# ESP-AXA.net
KiCad netlist of a schematic drawn in EAGLE
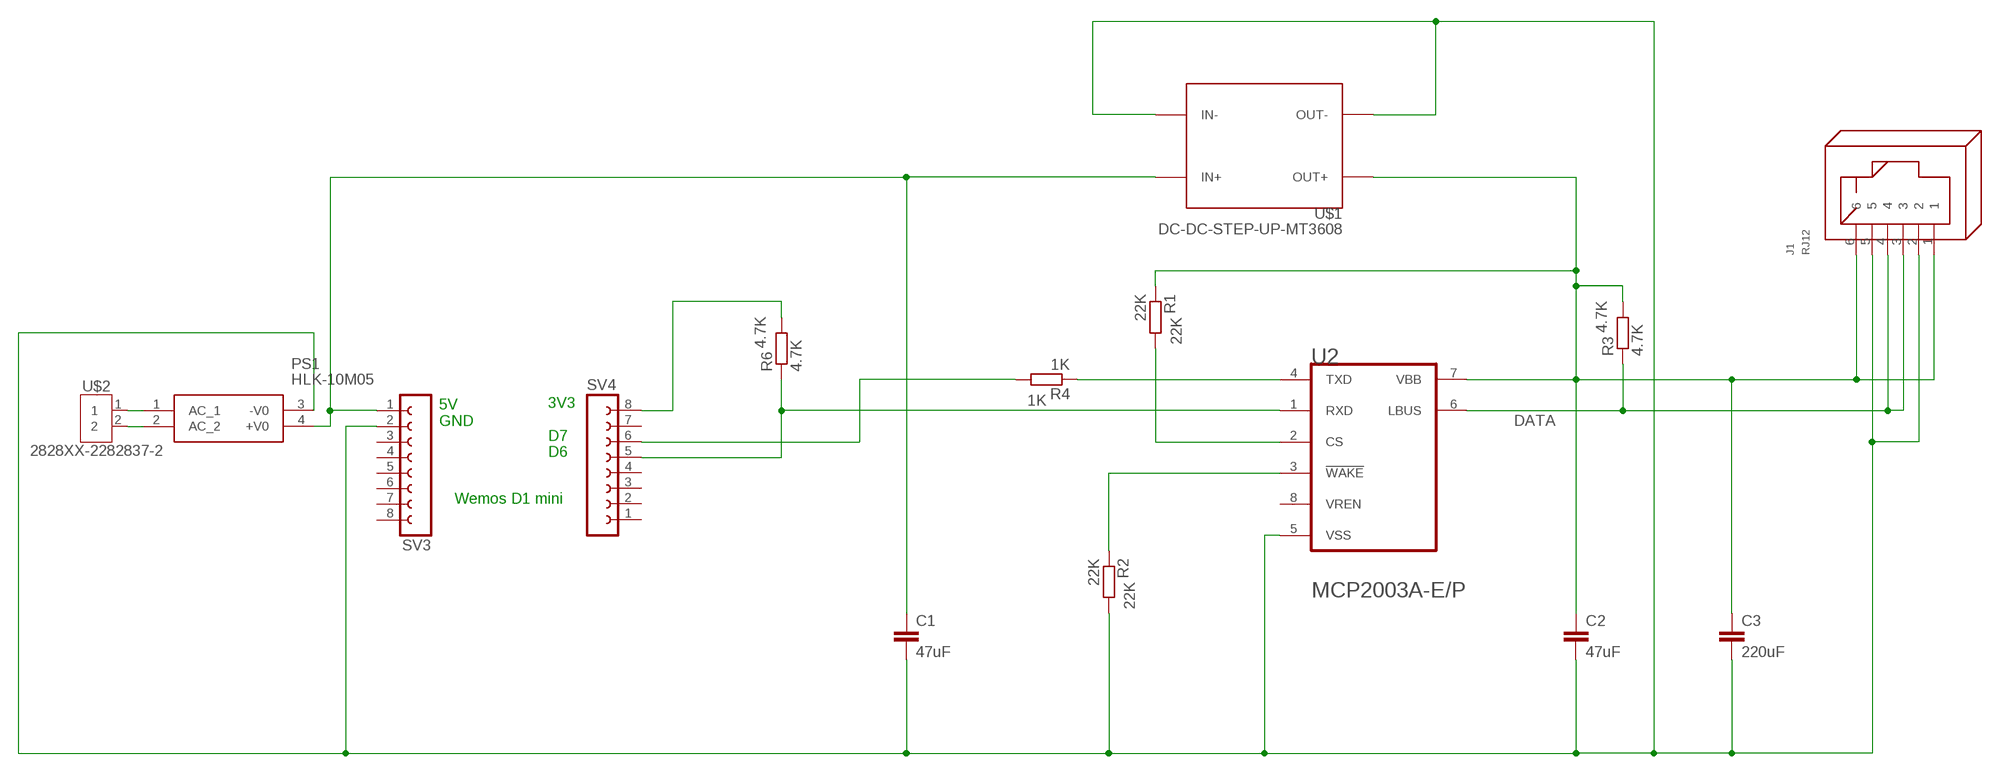
[diagram p0: schematic, sheet 1]

(export (version "E")
  (design (tool "Eeschema 10.0.6"))
  (components
    (comp (ref "C1")
      (value "47uF")
      (footprint "eagle-import:C7.5B3")
      (libsource (lib "eagle-import") (part "C7.5/3"))
    )
    (comp (ref "C2")
      (value "47uF")
      (footprint "eagle-import:C7.5B3")
      (libsource (lib "eagle-import") (part "C7.5/3"))
    )
    (comp (ref "C3")
      (value "220uF")
      (footprint "eagle-import:C7.5B3")
      (libsource (lib "eagle-import") (part "C7.5/3"))
    )
    (comp (ref "J1")
      (value "RJ12")
      (footprint "eagle-import:RJ12")
      (libsource (lib "eagle-import") (part "RJ12"))
    )
    (comp (ref "PS1")
      (value "HLK-10M05")
      (footprint "eagle-import:HLK10M05")
      (libsource (lib "eagle-import") (part "HLK-10M05"))
    )
    (comp (ref "R1")
      (value "22K")
      (footprint "eagle-import:0204V")
      (fields (field (name "R6") "22K"))
      (libsource (lib "eagle-import") (part "R-EU_0204/2V"))
    )
    (comp (ref "R2")
      (value "22K")
      (footprint "eagle-import:0204V")
      (fields (field (name "R6") "22K"))
      (libsource (lib "eagle-import") (part "R-EU_0204/2V"))
    )
    (comp (ref "R3")
      (value "4.7K")
      (footprint "eagle-import:0204V")
      (fields (field (name "R6") "4.7K"))
      (libsource (lib "eagle-import") (part "R-EU_0204/2V"))
    )
    (comp (ref "R4")
      (value "1K")
      (footprint "eagle-import:0204V")
      (fields (field (name "R6") "1K"))
      (libsource (lib "eagle-import") (part "R-EU_0204/2V"))
    )
    (comp (ref "R6")
      (value "4.7K")
      (footprint "eagle-import:0204V")
      (fields (field (name "R6") "4.7K"))
      (libsource (lib "eagle-import") (part "R-EU_0204/2V"))
    )
    (comp (ref "SV3")
      (value "FE08-1")
      (footprint "eagle-import:FE08")
      (libsource (lib "eagle-import") (part "FE08-1"))
    )
    (comp (ref "SV4")
      (value "FE08-1")
      (footprint "eagle-import:FE08")
      (libsource (lib "eagle-import") (part "FE08-1"))
    )
    (comp (ref "U$1")
      (value "DC-DC-STEP-UP-MT3608")
      (footprint "eagle-import:DC-DC-STEP-UP-MT3608")
      (libsource (lib "eagle-import") (part "DC-DC-STEP-UP-MT3608"))
    )
    (comp (ref "U$2")
      (value "2828XX-2282837-2")
      (footprint "eagle-import:TERMBLK_508-2N")
      (fields (field (name "MANUFACTURER") "TE Connectivity") (field (name "MPN") "282837-2"))
      (libsource (lib "eagle-import") (part "2828XX-2282837-2"))
    )
    (comp (ref "U2")
      (value "MICROCHIP_MCP2003A-E-PMICROCHIP_MCP2003A-E-P_0_0")
      (footprint "eagle-import:MICROCHIP_MCP2003A-E-P_0")
      (fields (field (name "MF") "Microchip") (field (name "MPN") "MCP2003A-E/P"))
      (libsource (lib "eagle-import") (part "MICROCHIP_MCP2003A-E-PMICROCHIP_MCP2003A-E-P_0_0"))
    )
  )
  (nets
    (net (code "1") (name "/DATA") (class "Default")
      (node (ref "J1") (pin "3") (pinfunction "3_3") (pintype "bidirectional"))
      (node (ref "J1") (pin "4") (pinfunction "4_4") (pintype "bidirectional"))
      (node (ref "R3") (pin "1") (pinfunction "1_1") (pintype "passive"))
      (node (ref "U2") (pin "6") (pinfunction "LBUS_6") (pintype "bidirectional"))
    )
    (net (code "2") (name "Net-(PS1-+V0)") (class "Default")
      (node (ref "C1") (pin "1") (pinfunction "1_1") (pintype "passive"))
      (node (ref "PS1") (pin "4") (pinfunction "+V0_4") (pintype "bidirectional"))
      (node (ref "SV3") (pin "1") (pinfunction "1_1") (pintype "passive"))
      (node (ref "U$1") (pin "IN+") (pinfunction "IN+_IN+") (pintype "bidirectional"))
    )
    (net (code "3") (name "Net-(PS1--V0)") (class "Default")
      (node (ref "C1") (pin "2") (pinfunction "2_2") (pintype "passive"))
      (node (ref "C2") (pin "2") (pinfunction "2_2") (pintype "passive"))
      (node (ref "C3") (pin "2") (pinfunction "2_2") (pintype "passive"))
      (node (ref "J1") (pin "2") (pinfunction "2_2") (pintype "bidirectional"))
      (node (ref "J1") (pin "5") (pinfunction "5_5") (pintype "bidirectional"))
      (node (ref "PS1") (pin "3") (pinfunction "-V0_3") (pintype "bidirectional"))
      (node (ref "R2") (pin "2") (pinfunction "2_2") (pintype "passive"))
      (node (ref "SV3") (pin "2") (pinfunction "2_2") (pintype "passive"))
      (node (ref "U$1") (pin "IN-") (pinfunction "IN-_IN-") (pintype "bidirectional"))
      (node (ref "U$1") (pin "OUT-") (pinfunction "OUT-_OUT-") (pintype "bidirectional"))
      (node (ref "U2") (pin "5") (pinfunction "VSS_5") (pintype "power_in"))
    )
    (net (code "4") (name "Net-(PS1-AC_1)") (class "Default")
      (node (ref "PS1") (pin "1") (pinfunction "AC_1_1") (pintype "bidirectional"))
      (node (ref "U$2") (pin "1") (pinfunction "1_1") (pintype "bidirectional"))
    )
    (net (code "5") (name "Net-(PS1-AC_2)") (class "Default")
      (node (ref "PS1") (pin "2") (pinfunction "AC_2_2") (pintype "bidirectional"))
      (node (ref "U$2") (pin "2") (pinfunction "2_2") (pintype "bidirectional"))
    )
    (net (code "6") (name "Net-(R4-Pad2)") (class "Default")
      (node (ref "R4") (pin "2") (pinfunction "2_2") (pintype "passive"))
      (node (ref "SV4") (pin "6") (pinfunction "6_6") (pintype "passive"))
    )
    (net (code "7") (name "Net-(R6-Pad2)") (class "Default")
      (node (ref "R6") (pin "2") (pinfunction "2_2") (pintype "passive"))
      (node (ref "SV4") (pin "8") (pinfunction "8_8") (pintype "passive"))
    )
    (net (code "8") (name "Net-(U2-CS)") (class "Default")
      (node (ref "R1") (pin "2") (pinfunction "2_2") (pintype "passive"))
      (node (ref "U2") (pin "2") (pinfunction "CS_2") (pintype "input"))
    )
    (net (code "9") (name "Net-(U2-RXD)") (class "Default")
      (node (ref "R6") (pin "1") (pinfunction "1_1") (pintype "passive"))
      (node (ref "SV4") (pin "5") (pinfunction "5_5") (pintype "passive"))
      (node (ref "U2") (pin "1") (pinfunction "RXD_1") (pintype "open_collector"))
    )
    (net (code "10") (name "Net-(U2-TXD)") (class "Default")
      (node (ref "R4") (pin "1") (pinfunction "1_1") (pintype "passive"))
      (node (ref "U2") (pin "4") (pinfunction "TXD_4") (pintype "input"))
    )
    (net (code "11") (name "Net-(U2-VBB)") (class "Default")
      (node (ref "C2") (pin "1") (pinfunction "1_1") (pintype "passive"))
      (node (ref "C3") (pin "1") (pinfunction "1_1") (pintype "passive"))
      (node (ref "J1") (pin "1") (pinfunction "1_1") (pintype "bidirectional"))
      (node (ref "J1") (pin "6") (pinfunction "6_6") (pintype "bidirectional"))
      (node (ref "R1") (pin "1") (pinfunction "1_1") (pintype "passive"))
      (node (ref "R3") (pin "2") (pinfunction "2_2") (pintype "passive"))
      (node (ref "U$1") (pin "OUT+") (pinfunction "OUT+_OUT+") (pintype "bidirectional"))
      (node (ref "U2") (pin "7") (pinfunction "VBB_7") (pintype "power_in"))
    )
    (net (code "12") (name "Net-(U2-~{WAKE})") (class "Default")
      (node (ref "R2") (pin "1") (pinfunction "1_1") (pintype "passive"))
      (node (ref "U2") (pin "3") (pinfunction "~{WAKE}_3") (pintype "input"))
    )
    (net (code "13") (name "unconnected-(SV3-Pad3)") (class "Default")
      (node (ref "SV3") (pin "3") (pinfunction "3_3") (pintype "passive"))
    )
    (net (code "14") (name "unconnected-(SV3-Pad4)") (class "Default")
      (node (ref "SV3") (pin "4") (pinfunction "4_4") (pintype "passive"))
    )
    (net (code "15") (name "unconnected-(SV3-Pad5)") (class "Default")
      (node (ref "SV3") (pin "5") (pinfunction "5_5") (pintype "passive"))
    )
    (net (code "16") (name "unconnected-(SV3-Pad6)") (class "Default")
      (node (ref "SV3") (pin "6") (pinfunction "6_6") (pintype "passive"))
    )
    (net (code "17") (name "unconnected-(SV3-Pad7)") (class "Default")
      (node (ref "SV3") (pin "7") (pinfunction "7_7") (pintype "passive"))
    )
    (net (code "18") (name "unconnected-(SV3-Pad8)") (class "Default")
      (node (ref "SV3") (pin "8") (pinfunction "8_8") (pintype "passive"))
    )
    (net (code "19") (name "unconnected-(SV4-Pad1)") (class "Default")
      (node (ref "SV4") (pin "1") (pinfunction "1_1") (pintype "passive"))
    )
    (net (code "20") (name "unconnected-(SV4-Pad2)") (class "Default")
      (node (ref "SV4") (pin "2") (pinfunction "2_2") (pintype "passive"))
    )
    (net (code "21") (name "unconnected-(SV4-Pad3)") (class "Default")
      (node (ref "SV4") (pin "3") (pinfunction "3_3") (pintype "passive"))
    )
    (net (code "22") (name "unconnected-(SV4-Pad4)") (class "Default")
      (node (ref "SV4") (pin "4") (pinfunction "4_4") (pintype "passive"))
    )
    (net (code "23") (name "unconnected-(SV4-Pad7)") (class "Default")
      (node (ref "SV4") (pin "7") (pinfunction "7_7") (pintype "passive"))
    )
    (net (code "24") (name "unconnected-(U2-VREN-Pad8)") (class "Default")
      (node (ref "U2") (pin "8") (pinfunction "VREN_8") (pintype "output"))
    )
  )
)
